# Power.net
KiCad netlist of a schematic drawn in Altium Designer
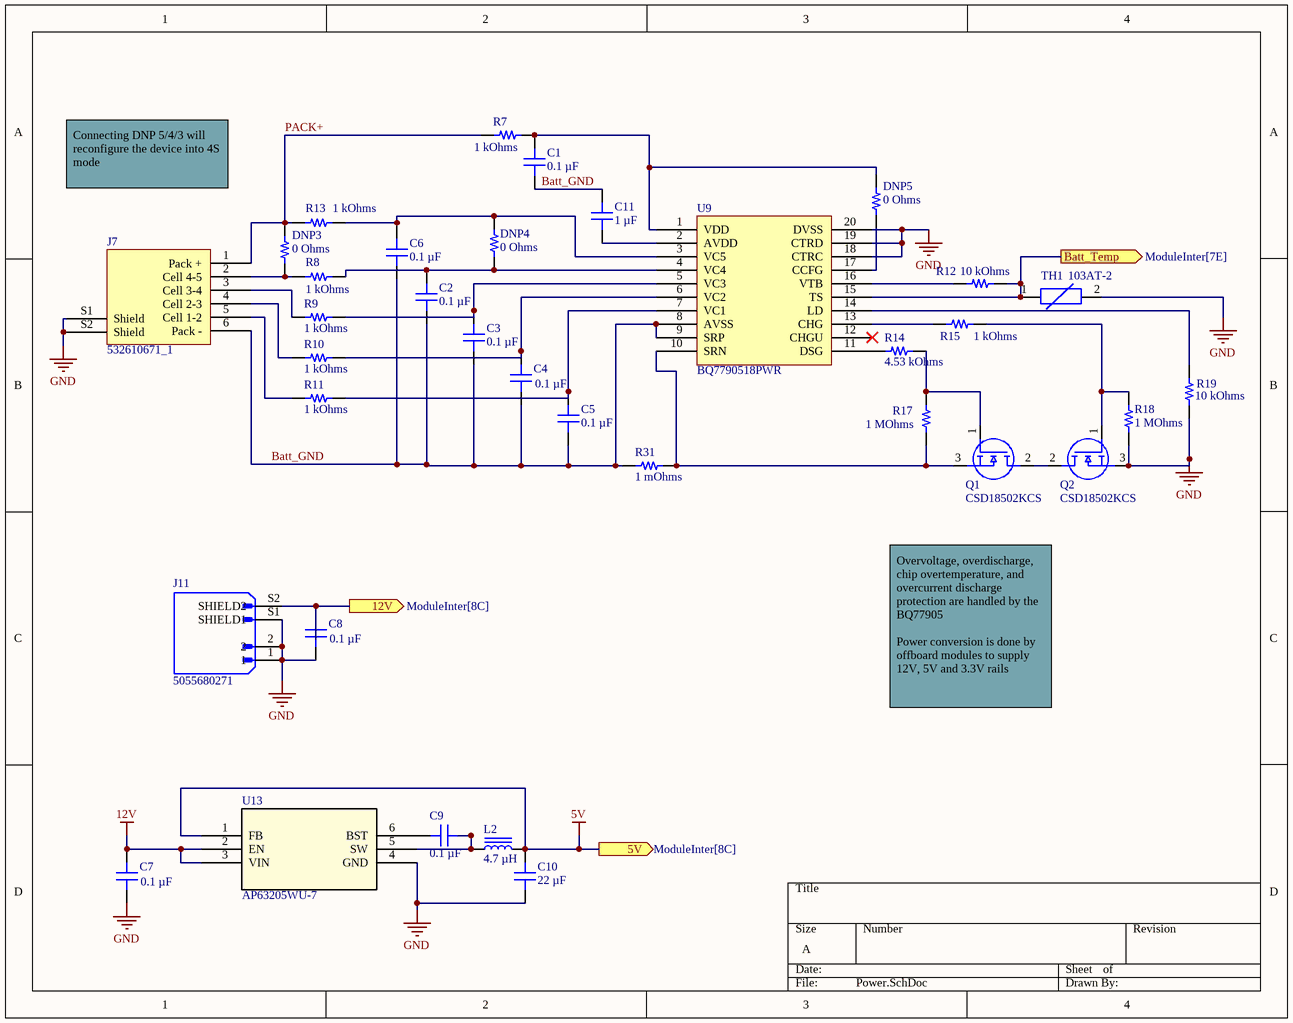
[diagram p0: Power.SchDoc]

(export (version "E")
  (design (tool "Eeschema 10.0.6"))
  (components
    (comp (ref "C1")
      (value "0.1 µF")
      (footprint "CAP 1206_3216 - 0.8MM")
      (description "CAP CER 0.1UF 50V Y5V 1206")
      (fields (field (name "PART NUMBER") "CC1206MRY5V9BB104") (field (name "MANUFACTURER") "Yageo"))
      (libsource (lib "Celestial Altium Library - altium_library") (part "Capacitor"))
    )
    (comp (ref "C2")
      (value "0.1 µF")
      (footprint "CAP 1206_3216 - 0.8MM")
      (description "CAP CER 0.1UF 50V Y5V 1206")
      (fields (field (name "PART NUMBER") "CC1206MRY5V9BB104") (field (name "MANUFACTURER") "Yageo"))
      (libsource (lib "Celestial Altium Library - altium_library") (part "Capacitor"))
    )
    (comp (ref "C3")
      (value "0.1 µF")
      (footprint "CAP 1206_3216 - 0.8MM")
      (description "CAP CER 0.1UF 50V Y5V 1206")
      (fields (field (name "PART NUMBER") "CC1206MRY5V9BB104") (field (name "MANUFACTURER") "Yageo"))
      (libsource (lib "Celestial Altium Library - altium_library") (part "Capacitor"))
    )
    (comp (ref "C4")
      (value "0.1 µF")
      (footprint "CAP 1206_3216 - 0.8MM")
      (description "CAP CER 0.1UF 50V Y5V 1206")
      (fields (field (name "PART NUMBER") "CC1206MRY5V9BB104") (field (name "MANUFACTURER") "Yageo"))
      (libsource (lib "Celestial Altium Library - altium_library") (part "Capacitor"))
    )
    (comp (ref "C5")
      (value "0.1 µF")
      (footprint "CAP 1206_3216 - 0.8MM")
      (description "CAP CER 0.1UF 50V Y5V 1206")
      (fields (field (name "PART NUMBER") "CC1206MRY5V9BB104") (field (name "MANUFACTURER") "Yageo"))
      (libsource (lib "Celestial Altium Library - altium_library") (part "Capacitor"))
    )
    (comp (ref "C6")
      (value "0.1 µF")
      (footprint "CAP 1206_3216 - 0.8MM")
      (description "CAP CER 0.1UF 50V Y5V 1206")
      (fields (field (name "PART NUMBER") "CC1206MRY5V9BB104") (field (name "MANUFACTURER") "Yageo"))
      (libsource (lib "Celestial Altium Library - altium_library") (part "Capacitor"))
    )
    (comp (ref "C7")
      (value "0.1 µF")
      (footprint "CAP 1206_3216 - 0.8MM")
      (description "CAP CER 0.1UF 50V Y5V 1206")
      (fields (field (name "PART NUMBER") "CC1206MRY5V9BB104") (field (name "MANUFACTURER") "Yageo"))
      (libsource (lib "Celestial Altium Library - altium_library") (part "Capacitor"))
    )
    (comp (ref "C8")
      (value "0.1 µF")
      (footprint "CAP 1206_3216 - 0.8MM")
      (description "CAP CER 0.1UF 50V Y5V 1206")
      (fields (field (name "PART NUMBER") "CC1206MRY5V9BB104") (field (name "MANUFACTURER") "Yageo"))
      (libsource (lib "Celestial Altium Library - altium_library") (part "Capacitor"))
    )
    (comp (ref "C9")
      (value "0.1 µF")
      (footprint "CAP 1206_3216 - 0.8MM")
      (description "CAP CER 0.1UF 50V Y5V 1206")
      (fields (field (name "PART NUMBER") "CC1206MRY5V9BB104") (field (name "MANUFACTURER") "Yageo"))
      (libsource (lib "Celestial Altium Library - altium_library") (part "Capacitor"))
    )
    (comp (ref "C10")
      (value "22 µF")
      (footprint "CAP 0805_2012")
      (description "CAP CER 22UF 16V X5R 0805")
      (fields
        (field (name "PART NUMBER") "CL21A226KOQNNNG")
        (field (name "MANUFACTURER") "Samsung Electro-Mechanics")
      )
      (libsource (lib "Celestial Altium Library - altium_library") (part "Capacitor"))
    )
    (comp (ref "C11")
      (value "1 µF")
      (footprint "CAP 0805_2012")
      (description "CAP CER 1UF 50V X7R 0805")
      (fields
        (field (name "PART NUMBER") "GCJ21BR71H105KA01L")
        (field (name "MANUFACTURER") "Murata Electronics")
      )
      (libsource (lib "Celestial Altium Library - altium_library") (part "Capacitor"))
    )
    (comp (ref "DNP3")
      (value "0 Ohms")
      (footprint "RES 1206_3216")
      (description "RES 0 OHM JUMPER 1/2W 1206")
      (fields (field (name "PART NUMBER") "RC1206JR-7W0RL") (field (name "MANUFACTURER") "Yageo"))
      (libsource (lib "Celestial Altium Library - altium_library") (part "Resistor"))
    )
    (comp (ref "DNP4")
      (value "0 Ohms")
      (footprint "RES 1206_3216")
      (description "RES 0 OHM JUMPER 1/2W 1206")
      (fields (field (name "PART NUMBER") "RC1206JR-7W0RL") (field (name "MANUFACTURER") "Yageo"))
      (libsource (lib "Celestial Altium Library - altium_library") (part "Resistor"))
    )
    (comp (ref "DNP5")
      (value "0 Ohms")
      (footprint "RES 1206_3216")
      (description "RES 0 OHM JUMPER 1/2W 1206")
      (fields (field (name "PART NUMBER") "RC1206JR-7W0RL") (field (name "MANUFACTURER") "Yageo"))
      (libsource (lib "Celestial Altium Library - altium_library") (part "Resistor"))
    )
    (comp (ref "J7")
      (value "532610671_1")
      (footprint "MOLEX_532610671")
      (description "Conn Shrouded Header (4 Sides) HDR 6 POS 1.25mm Solder RA Side Entry SMD PicoBlade™ T/R")
      (libsource (lib "CBSchLib") (part "532610671_1"))
    )
    (comp (ref "J11")
      (value "5055680271")
      (footprint "MOLEX_5055680271")
      (fields (field (name "MF") "Molex"))
      (libsource (lib "CBSchLib") (part "5055680271"))
    )
    (comp (ref "L2")
      (value "4.7 µH")
      (footprint "BOURNS SRP5030T")
      (description "FIXED IND 4.7UH 4.6A 53 MOHM SMD")
      (fields (field (name "PART NUMBER") "SRP5030T-4R7M") (field (name "MANUFACTURER") "Bourns Inc."))
      (libsource (lib "Celestial Altium Library - altium_library") (part "Inductor"))
    )
    (comp (ref "Q1")
      (value "CSD18502KCS")
      (footprint "TO254P470X1016X2005-3P")
      (description "40V, N ch NexFET MOSFET, single TO-220, 2.9mOhm")
      (fields (field (name "MOUSER PART NUMBER") "595-CSD18502KCS"))
      (libsource (lib "CBSchLib") (part "CSD18502KCS"))
    )
    (comp (ref "Q2")
      (value "CSD18502KCS")
      (footprint "TO254P470X1016X2005-3P")
      (description "40V, N ch NexFET MOSFET, single TO-220, 2.9mOhm")
      (fields (field (name "MOUSER PART NUMBER") "595-CSD18502KCS"))
      (libsource (lib "CBSchLib") (part "CSD18502KCS"))
    )
    (comp (ref "R7")
      (value "1 kOhms")
      (footprint "RES 1206_3216")
      (description "RES 1K OHM 0.1% 1/8W 1206")
      (fields
        (field (name "PART NUMBER") "RNCS1206BKE1K00")
        (field (name "MANUFACTURER") "Stackpole Electronics Inc")
      )
      (libsource (lib "Celestial Altium Library - altium_library") (part "Resistor"))
    )
    (comp (ref "R8")
      (value "1 kOhms")
      (footprint "RES 1206_3216")
      (description "RES 1K OHM 0.1% 1/8W 1206")
      (fields
        (field (name "PART NUMBER") "RNCS1206BKE1K00")
        (field (name "MANUFACTURER") "Stackpole Electronics Inc")
      )
      (libsource (lib "Celestial Altium Library - altium_library") (part "Resistor"))
    )
    (comp (ref "R9")
      (value "1 kOhms")
      (footprint "RES 1206_3216")
      (description "RES 1K OHM 0.1% 1/8W 1206")
      (fields
        (field (name "PART NUMBER") "RNCS1206BKE1K00")
        (field (name "MANUFACTURER") "Stackpole Electronics Inc")
      )
      (libsource (lib "Celestial Altium Library - altium_library") (part "Resistor"))
    )
    (comp (ref "R10")
      (value "1 kOhms")
      (footprint "RES 1206_3216")
      (description "RES 1K OHM 0.1% 1/8W 1206")
      (fields
        (field (name "PART NUMBER") "RNCS1206BKE1K00")
        (field (name "MANUFACTURER") "Stackpole Electronics Inc")
      )
      (libsource (lib "Celestial Altium Library - altium_library") (part "Resistor"))
    )
    (comp (ref "R11")
      (value "1 kOhms")
      (footprint "RES 1206_3216")
      (description "RES 1K OHM 0.1% 1/8W 1206")
      (fields
        (field (name "PART NUMBER") "RNCS1206BKE1K00")
        (field (name "MANUFACTURER") "Stackpole Electronics Inc")
      )
      (libsource (lib "Celestial Altium Library - altium_library") (part "Resistor"))
    )
    (comp (ref "R12")
      (value "10 kOhms")
      (footprint "RES 1206_3216")
      (description "RES SMD 10K OHM 1% 1/4W 1206")
      (fields
        (field (name "PART NUMBER") "CRG1206F10K")
        (field (name "MANUFACTURER") "TE Connectivity Passive Product")
      )
      (libsource (lib "Celestial Altium Library - altium_library") (part "Resistor"))
    )
    (comp (ref "R13")
      (value "1 kOhms")
      (footprint "RES 1206_3216")
      (description "RES 1K OHM 0.1% 1/8W 1206")
      (fields
        (field (name "PART NUMBER") "RNCS1206BKE1K00")
        (field (name "MANUFACTURER") "Stackpole Electronics Inc")
      )
      (libsource (lib "Celestial Altium Library - altium_library") (part "Resistor"))
    )
    (comp (ref "R14")
      (value "4.53 kOhms")
      (footprint "RES 1206_3216")
      (description "RES 4.53K OHM 1% 1/2W 1206")
      (fields
        (field (name "PART NUMBER") "RNCP1206FTD4K53")
        (field (name "MANUFACTURER") "Stackpole Electronics Inc")
      )
      (libsource (lib "Celestial Altium Library - altium_library") (part "Resistor"))
    )
    (comp (ref "R15")
      (value "1 kOhms")
      (footprint "RES 0805_2012")
      (description "RES 1K OHM 5% 1/4W 0805")
      (fields (field (name "PART NUMBER") "SR0805JR-7W1KL") (field (name "MANUFACTURER") "Yageo"))
      (libsource (lib "Celestial Altium Library - altium_library") (part "Resistor"))
    )
    (comp (ref "R17")
      (value "1 MOhms")
      (footprint "RES 1206_3216")
      (description "MCA 1206-25 0.1% AT P1 1M0")
      (fields
        (field (name "PART NUMBER") "MCA1206MD1004BP100")
        (field (name "MANUFACTURER") "Vishay Beyschlag")
      )
      (libsource (lib "Celestial Altium Library - altium_library") (part "Resistor"))
    )
    (comp (ref "R18")
      (value "1 MOhms")
      (footprint "RES 1206_3216")
      (description "MCA 1206-25 0.1% AT P1 1M0")
      (fields
        (field (name "PART NUMBER") "MCA1206MD1004BP100")
        (field (name "MANUFACTURER") "Vishay Beyschlag")
      )
      (libsource (lib "Celestial Altium Library - altium_library") (part "Resistor"))
    )
    (comp (ref "R19")
      (value "10 kOhms")
      (footprint "RES 1206_3216")
      (description "RES SMD 10K OHM 1% 1/4W 1206")
      (fields
        (field (name "PART NUMBER") "CRG1206F10K")
        (field (name "MANUFACTURER") "TE Connectivity Passive Product")
      )
      (libsource (lib "Celestial Altium Library - altium_library") (part "Resistor"))
    )
    (comp (ref "R31")
      (value "1 mOhms")
      (footprint "RES 0805_2012")
      (description "RES 0.001 OHM 1W 1% 0508 SMD")
      (fields
        (field (name "PART NUMBER") "CSS0508FT1L00")
        (field (name "MANUFACTURER") "Stackpole Electronics Inc")
      )
      (libsource (lib "Celestial Altium Library - altium_library") (part "Resistor"))
    )
    (comp (ref "TH1")
      (value "103AT-2")
      (footprint "103At-2")
      (description "NTC Thermistors 10kohm 1%")
      (libsource (lib "CBSchLib") (part "103AT-2"))
    )
    (comp (ref "U9")
      (value "BQ7790518PWR")
      (footprint "SOP65P640X120-20N")
      (libsource (lib "CBSchLib") (part "BQ7790518PWR"))
    )
    (comp (ref "U13")
      (value "AP63205WU-7")
      (footprint "SOIC_05WU-7_DIO")
      (description "No Description Available")
      (fields (field (name "COPYRIGHT") "Copyright (C) 2023 Ultra Librarian. All rights reserved."))
      (libsource (lib "CBSchLib") (part "AP63205WU-7"))
    )
  )
  (nets
    (net (code "1") (name "/Batt_GND") (class "Default")
      (node (ref "C1") (pin "1") (pinfunction "1_1") (pintype "passive"))
      (node (ref "C11") (pin "2") (pinfunction "2_2") (pintype "passive"))
      (node (ref "C2") (pin "1") (pinfunction "1_1") (pintype "passive"))
      (node (ref "C3") (pin "1") (pinfunction "1_1") (pintype "passive"))
      (node (ref "C4") (pin "1") (pinfunction "1_1") (pintype "passive"))
      (node (ref "C5") (pin "1") (pinfunction "1_1") (pintype "passive"))
      (node (ref "C6") (pin "1") (pinfunction "1_1") (pintype "passive"))
      (node (ref "J7") (pin "6") (pinfunction "Pack_-_6") (pintype "passive"))
      (node (ref "R31") (pin "1") (pinfunction "1_1") (pintype "passive"))
      (node (ref "U9") (pin "8") (pinfunction "AVSS_8") (pintype "passive"))
      (node (ref "U9") (pin "9") (pinfunction "SRP_9") (pintype "passive"))
    )
    (net (code "2") (name "/Batt_Temp") (class "Default")
      (node (ref "R12") (pin "1") (pinfunction "1_1") (pintype "passive"))
      (node (ref "TH1") (pin "1") (pinfunction "1_1") (pintype "passive"))
      (node (ref "U9") (pin "15") (pinfunction "TS_15") (pintype "passive"))
    )
    (net (code "3") (name "/PACK+") (class "Default")
      (node (ref "DNP3") (pin "2") (pinfunction "2_2") (pintype "passive"))
      (node (ref "J7") (pin "1") (pinfunction "Pack_+_1") (pintype "passive"))
      (node (ref "R13") (pin "1") (pinfunction "1_1") (pintype "passive"))
      (node (ref "R7") (pin "1") (pinfunction "1_1") (pintype "passive"))
    )
    (net (code "4") (name "5V") (class "Default")
      (node (ref "C10") (pin "2") (pinfunction "2_2") (pintype "passive"))
      (node (ref "L2") (pin "2") (pinfunction "2_2") (pintype "passive"))
      (node (ref "U13") (pin "1") (pinfunction "FB_1") (pintype "passive"))
    )
    (net (code "5") (name "12V") (class "Default")
      (node (ref "C7") (pin "2") (pinfunction "2_2") (pintype "passive"))
      (node (ref "C8") (pin "2") (pinfunction "2_2") (pintype "passive"))
      (node (ref "J11") (pin "S2") (pinfunction "SHIELD2_S2") (pintype "passive"))
      (node (ref "U13") (pin "2") (pinfunction "EN_2") (pintype "passive"))
      (node (ref "U13") (pin "3") (pinfunction "VIN_3") (pintype "passive"))
    )
    (net (code "6") (name "GND") (class "Default")
      (node (ref "C10") (pin "1") (pinfunction "1_1") (pintype "passive"))
      (node (ref "C7") (pin "1") (pinfunction "1_1") (pintype "passive"))
      (node (ref "C8") (pin "1") (pinfunction "1_1") (pintype "passive"))
      (node (ref "J11") (pin "1") (pinfunction "1_1") (pintype "passive"))
      (node (ref "J11") (pin "2") (pinfunction "2_2") (pintype "passive"))
      (node (ref "J11") (pin "S1") (pinfunction "SHIELD1_S1") (pintype "passive"))
      (node (ref "J7") (pin "S1") (pinfunction "Shield_S1") (pintype "passive"))
      (node (ref "J7") (pin "S2") (pinfunction "Shield_S2") (pintype "passive"))
      (node (ref "Q2") (pin "3") (pinfunction "S_3") (pintype "passive"))
      (node (ref "R18") (pin "1") (pinfunction "1_1") (pintype "passive"))
      (node (ref "R19") (pin "1") (pinfunction "1_1") (pintype "passive"))
      (node (ref "TH1") (pin "2") (pinfunction "2_2") (pintype "passive"))
      (node (ref "U13") (pin "4") (pinfunction "GND_4") (pintype "passive"))
      (node (ref "U9") (pin "18") (pinfunction "CTRC_18") (pintype "passive"))
      (node (ref "U9") (pin "19") (pinfunction "CTRD_19") (pintype "passive"))
      (node (ref "U9") (pin "20") (pinfunction "DVSS_20") (pintype "passive"))
    )
    (net (code "7") (name "Net-(J7-Cell_1-2)") (class "Default")
      (node (ref "J7") (pin "5") (pinfunction "Cell_1-2_5") (pintype "passive"))
      (node (ref "R11") (pin "1") (pinfunction "1_1") (pintype "passive"))
    )
    (net (code "8") (name "Net-(J7-Cell_2-3)") (class "Default")
      (node (ref "J7") (pin "4") (pinfunction "Cell_2-3_4") (pintype "passive"))
      (node (ref "R10") (pin "1") (pinfunction "1_1") (pintype "passive"))
    )
    (net (code "9") (name "Net-(J7-Cell_3-4)") (class "Default")
      (node (ref "J7") (pin "3") (pinfunction "Cell_3-4_3") (pintype "passive"))
      (node (ref "R9") (pin "1") (pinfunction "1_1") (pintype "passive"))
    )
    (net (code "10") (name "Net-(J7-Cell_4-5)") (class "Default")
      (node (ref "DNP3") (pin "1") (pinfunction "1_1") (pintype "passive"))
      (node (ref "J7") (pin "2") (pinfunction "Cell_4-5_2") (pintype "passive"))
      (node (ref "R8") (pin "1") (pinfunction "1_1") (pintype "passive"))
    )
    (net (code "11") (name "Net-(Q1-D)") (class "Default")
      (node (ref "Q1") (pin "2") (pinfunction "D_2") (pintype "passive"))
      (node (ref "Q2") (pin "2") (pinfunction "D_2") (pintype "passive"))
    )
    (net (code "12") (name "Net-(Q1-G)") (class "Default")
      (node (ref "Q1") (pin "1") (pinfunction "G_1") (pintype "passive"))
      (node (ref "R14") (pin "2") (pinfunction "2_2") (pintype "passive"))
      (node (ref "R17") (pin "1") (pinfunction "1_1") (pintype "passive"))
    )
    (net (code "13") (name "Net-(Q1-S)") (class "Default")
      (node (ref "Q1") (pin "3") (pinfunction "S_3") (pintype "passive"))
      (node (ref "R17") (pin "2") (pinfunction "2_2") (pintype "passive"))
      (node (ref "R31") (pin "2") (pinfunction "2_2") (pintype "passive"))
      (node (ref "U9") (pin "10") (pinfunction "SRN_10") (pintype "passive"))
    )
    (net (code "14") (name "Net-(Q2-G)") (class "Default")
      (node (ref "Q2") (pin "1") (pinfunction "G_1") (pintype "passive"))
      (node (ref "R15") (pin "2") (pinfunction "2_2") (pintype "passive"))
      (node (ref "R18") (pin "2") (pinfunction "2_2") (pintype "passive"))
    )
    (net (code "15") (name "Net-(U9-AVDD)") (class "Default")
      (node (ref "C11") (pin "1") (pinfunction "1_1") (pintype "passive"))
      (node (ref "U9") (pin "2") (pinfunction "AVDD_2") (pintype "passive"))
    )
    (net (code "16") (name "Net-(U9-CCFG)") (class "Default")
      (node (ref "DNP5") (pin "1") (pinfunction "1_1") (pintype "passive"))
      (node (ref "U9") (pin "17") (pinfunction "CCFG_17") (pintype "passive"))
    )
    (net (code "17") (name "Net-(U9-CHG)") (class "Default")
      (node (ref "R15") (pin "1") (pinfunction "1_1") (pintype "passive"))
      (node (ref "U9") (pin "13") (pinfunction "CHG_13") (pintype "passive"))
    )
    (net (code "18") (name "Net-(U9-DSG)") (class "Default")
      (node (ref "R14") (pin "1") (pinfunction "1_1") (pintype "passive"))
      (node (ref "U9") (pin "11") (pinfunction "DSG_11") (pintype "passive"))
    )
    (net (code "19") (name "Net-(U9-LD)") (class "Default")
      (node (ref "R19") (pin "2") (pinfunction "2_2") (pintype "passive"))
      (node (ref "U9") (pin "14") (pinfunction "LD_14") (pintype "passive"))
    )
    (net (code "20") (name "Net-(U9-VC1)") (class "Default")
      (node (ref "C5") (pin "2") (pinfunction "2_2") (pintype "passive"))
      (node (ref "R11") (pin "2") (pinfunction "2_2") (pintype "passive"))
      (node (ref "U9") (pin "7") (pinfunction "VC1_7") (pintype "passive"))
    )
    (net (code "21") (name "Net-(U9-VC2)") (class "Default")
      (node (ref "C4") (pin "2") (pinfunction "2_2") (pintype "passive"))
      (node (ref "R10") (pin "2") (pinfunction "2_2") (pintype "passive"))
      (node (ref "U9") (pin "6") (pinfunction "VC2_6") (pintype "passive"))
    )
    (net (code "22") (name "Net-(U9-VC3)") (class "Default")
      (node (ref "C3") (pin "2") (pinfunction "2_2") (pintype "passive"))
      (node (ref "R9") (pin "2") (pinfunction "2_2") (pintype "passive"))
      (node (ref "U9") (pin "5") (pinfunction "VC3_5") (pintype "passive"))
    )
    (net (code "23") (name "Net-(U9-VC4)") (class "Default")
      (node (ref "C2") (pin "2") (pinfunction "2_2") (pintype "passive"))
      (node (ref "DNP4") (pin "1") (pinfunction "1_1") (pintype "passive"))
      (node (ref "R8") (pin "2") (pinfunction "2_2") (pintype "passive"))
      (node (ref "U9") (pin "4") (pinfunction "VC4_4") (pintype "passive"))
    )
    (net (code "24") (name "Net-(U9-VC5)") (class "Default")
      (node (ref "C6") (pin "2") (pinfunction "2_2") (pintype "passive"))
      (node (ref "DNP4") (pin "2") (pinfunction "2_2") (pintype "passive"))
      (node (ref "R13") (pin "2") (pinfunction "2_2") (pintype "passive"))
      (node (ref "U9") (pin "3") (pinfunction "VC5_3") (pintype "passive"))
    )
    (net (code "25") (name "Net-(U9-VDD)") (class "Default")
      (node (ref "C1") (pin "2") (pinfunction "2_2") (pintype "passive"))
      (node (ref "DNP5") (pin "2") (pinfunction "2_2") (pintype "passive"))
      (node (ref "R7") (pin "2") (pinfunction "2_2") (pintype "passive"))
      (node (ref "U9") (pin "1") (pinfunction "VDD_1") (pintype "passive"))
    )
    (net (code "26") (name "Net-(U9-VTB)") (class "Default")
      (node (ref "R12") (pin "2") (pinfunction "2_2") (pintype "passive"))
      (node (ref "U9") (pin "16") (pinfunction "VTB_16") (pintype "passive"))
    )
    (net (code "27") (name "Net-(U13-BST)") (class "Default")
      (node (ref "C9") (pin "2") (pinfunction "2_2") (pintype "passive"))
      (node (ref "U13") (pin "6") (pinfunction "BST_6") (pintype "passive"))
    )
    (net (code "28") (name "Net-(U13-SW)") (class "Default")
      (node (ref "C9") (pin "1") (pinfunction "1_1") (pintype "passive"))
      (node (ref "L2") (pin "1") (pinfunction "1_1") (pintype "passive"))
      (node (ref "U13") (pin "5") (pinfunction "SW_5") (pintype "passive"))
    )
    (net (code "29") (name "unconnected-(U9-CHGU-Pad12)") (class "Default")
      (node (ref "U9") (pin "12") (pinfunction "CHGU_12") (pintype "passive+no_connect"))
    )
  )
)
